# led_driver.net
KiCad netlist of a schematic drawn in EAGLE
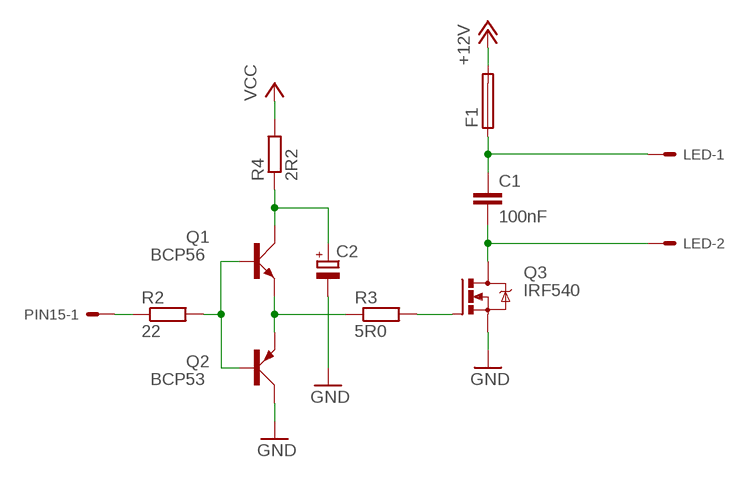
[diagram p0: schematic, sheet 1]

(export (version "E")
  (design (tool "Eeschema 10.0.6"))
  (components
    (comp (ref "C1")
      (value "100nF")
      (footprint "eagle-import:C2.5-3")
      (libsource (lib "eagle-import") (part "C2,5-3"))
    )
    (comp (ref "C2")
      (value "CPOL-EU085CS-1AR")
      (footprint "eagle-import:085CS_1AR")
      (libsource (lib "eagle-import") (part "CPOL-EU085CS-1AR"))
    )
    (comp (ref "F1")
      (value "TE5")
      (footprint "eagle-import:TE5")
      (libsource (lib "eagle-import") (part "TE5"))
    )
    (comp (ref "LED")
      (value "5566-10")
      (footprint "eagle-import:5566-10")
      (libsource (lib "eagle-import") (part "5566-10"))
    )
    (comp (ref "PIN15")
      (value "5566-10")
      (footprint "eagle-import:5566-10")
      (libsource (lib "eagle-import") (part "5566-10"))
    )
    (comp (ref "Q1")
      (value "BCP56")
      (footprint "eagle-import:SOT54D")
      (libsource (lib "eagle-import") (part "BC639"))
    )
    (comp (ref "Q2")
      (value "BCP53")
      (footprint "eagle-import:SOT54D")
      (libsource (lib "eagle-import") (part "BC640"))
    )
    (comp (ref "Q3")
      (value "IRF540")
      (footprint "eagle-import:TO220BV")
      (libsource (lib "eagle-import") (part "IRF540"))
    )
    (comp (ref "R2")
      (value "22")
      (footprint "eagle-import:R1206")
      (libsource (lib "eagle-import") (part "R-EU_R1206"))
    )
    (comp (ref "R3")
      (value "5R0")
      (footprint "eagle-import:R1206")
      (libsource (lib "eagle-import") (part "R-EU_R1206"))
    )
    (comp (ref "R4")
      (value "2R2")
      (footprint "eagle-import:R1206")
      (libsource (lib "eagle-import") (part "R-EU_R1206"))
    )
  )
  (nets
    (net (code "1") (name "+12V") (class "Default")
      (node (ref "F1") (pin "2") (pinfunction "2_2") (pintype "passive"))
    )
    (net (code "2") (name "GND") (class "Default")
      (node (ref "C2") (pin "-") (pinfunction "-_-") (pintype "passive"))
      (node (ref "Q2") (pin "C") (pinfunction "C_C") (pintype "passive"))
      (node (ref "Q3") (pin "S") (pinfunction "S_S") (pintype "passive"))
    )
    (net (code "3") (name "Net-(C2-Pad+)") (class "Default")
      (node (ref "C2") (pin "+") (pinfunction "+_+") (pintype "passive"))
      (node (ref "Q1") (pin "C") (pinfunction "C_C") (pintype "passive"))
      (node (ref "R4") (pin "1") (pinfunction "1_1") (pintype "passive"))
    )
    (net (code "4") (name "Net-(LEDA-S)") (class "Default")
      (node (ref "C1") (pin "1") (pinfunction "1_1") (pintype "passive"))
      (node (ref "F1") (pin "1") (pinfunction "1_1") (pintype "passive"))
      (node (ref "LED") (pin "1") (pinfunction "S_1") (pintype "passive"))
    )
    (net (code "5") (name "Net-(LEDC-S)") (class "Default")
      (node (ref "C1") (pin "2") (pinfunction "2_2") (pintype "passive"))
      (node (ref "LED") (pin "2") (pinfunction "S_2") (pintype "passive"))
      (node (ref "Q3") (pin "D") (pinfunction "D_D") (pintype "passive"))
    )
    (net (code "6") (name "Net-(PIN15A-S)") (class "Default")
      (node (ref "PIN15") (pin "1") (pinfunction "S_1") (pintype "passive"))
      (node (ref "R2") (pin "1") (pinfunction "1_1") (pintype "passive"))
    )
    (net (code "7") (name "Net-(Q1-PadB)") (class "Default")
      (node (ref "Q1") (pin "B") (pinfunction "B_B") (pintype "passive"))
      (node (ref "Q2") (pin "B") (pinfunction "B_B") (pintype "passive"))
      (node (ref "R2") (pin "2") (pinfunction "2_2") (pintype "passive"))
    )
    (net (code "8") (name "Net-(Q1-PadE)") (class "Default")
      (node (ref "Q1") (pin "E") (pinfunction "E_E") (pintype "passive"))
      (node (ref "Q2") (pin "E") (pinfunction "E_E") (pintype "passive"))
      (node (ref "R3") (pin "1") (pinfunction "1_1") (pintype "passive"))
    )
    (net (code "9") (name "Net-(Q3-PadG)") (class "Default")
      (node (ref "Q3") (pin "G") (pinfunction "G_G") (pintype "passive"))
      (node (ref "R3") (pin "2") (pinfunction "2_2") (pintype "passive"))
    )
    (net (code "10") (name "VCC") (class "Default")
      (node (ref "R4") (pin "2") (pinfunction "2_2") (pintype "passive"))
    )
  )
)
